# phase2.net
KiCad netlist of a schematic drawn in EAGLE
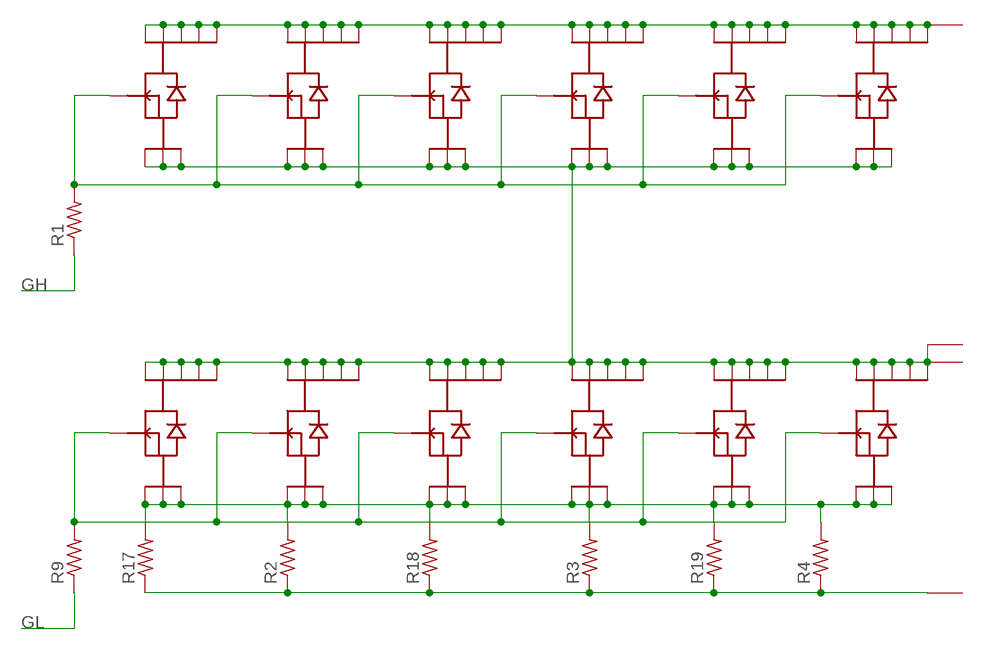
[diagram p0: schematic, sheet 1]

(export (version "E")
  (design (tool "Eeschema 10.0.6"))
  (components
    (comp (ref "R1")
      (value "R-US_R1206")
      (footprint "eagle-import:R1206")
      (libsource (lib "eagle-import") (part "R-US_R1206"))
    )
    (comp (ref "R2")
      (value "R-US_M1206")
      (footprint "eagle-import:M1206")
      (libsource (lib "eagle-import") (part "R-US_M1206"))
    )
    (comp (ref "R3")
      (value "R-US_M1206")
      (footprint "eagle-import:M1206")
      (libsource (lib "eagle-import") (part "R-US_M1206"))
    )
    (comp (ref "R4")
      (value "R-US_M1206")
      (footprint "eagle-import:M1206")
      (libsource (lib "eagle-import") (part "R-US_M1206"))
    )
    (comp (ref "R9")
      (value "R-US_R1206")
      (footprint "eagle-import:R1206")
      (libsource (lib "eagle-import") (part "R-US_R1206"))
    )
    (comp (ref "R17")
      (value "R-US_M1206")
      (footprint "eagle-import:M1206")
      (libsource (lib "eagle-import") (part "R-US_M1206"))
    )
    (comp (ref "R18")
      (value "R-US_M1206")
      (footprint "eagle-import:M1206")
      (libsource (lib "eagle-import") (part "R-US_M1206"))
    )
    (comp (ref "R19")
      (value "R-US_M1206")
      (footprint "eagle-import:M1206")
      (libsource (lib "eagle-import") (part "R-US_M1206"))
    )
    (comp (ref "U$1")
      (value "TPH2R608NH")
      (footprint "eagle-import:SOP-ADVANCE")
      (libsource (lib "eagle-import") (part "TPH2R608NH"))
    )
    (comp (ref "U$2")
      (value "TPH2R608NH")
      (footprint "eagle-import:SOP-ADVANCE")
      (libsource (lib "eagle-import") (part "TPH2R608NH"))
    )
    (comp (ref "U$3")
      (value "TPH2R608NH")
      (footprint "eagle-import:SOP-ADVANCE")
      (libsource (lib "eagle-import") (part "TPH2R608NH"))
    )
    (comp (ref "U$4")
      (value "TPH2R608NH")
      (footprint "eagle-import:SOP-ADVANCE")
      (libsource (lib "eagle-import") (part "TPH2R608NH"))
    )
    (comp (ref "U$5")
      (value "TPH2R608NH")
      (footprint "eagle-import:SOP-ADVANCE")
      (libsource (lib "eagle-import") (part "TPH2R608NH"))
    )
    (comp (ref "U$6")
      (value "TPH2R608NH")
      (footprint "eagle-import:SOP-ADVANCE")
      (libsource (lib "eagle-import") (part "TPH2R608NH"))
    )
    (comp (ref "U$9")
      (value "TPH2R608NH")
      (footprint "eagle-import:SOP-ADVANCE")
      (libsource (lib "eagle-import") (part "TPH2R608NH"))
    )
    (comp (ref "U$10")
      (value "TPH2R608NH")
      (footprint "eagle-import:SOP-ADVANCE")
      (libsource (lib "eagle-import") (part "TPH2R608NH"))
    )
    (comp (ref "U$11")
      (value "TPH2R608NH")
      (footprint "eagle-import:SOP-ADVANCE")
      (libsource (lib "eagle-import") (part "TPH2R608NH"))
    )
    (comp (ref "U$12")
      (value "TPH2R608NH")
      (footprint "eagle-import:SOP-ADVANCE")
      (libsource (lib "eagle-import") (part "TPH2R608NH"))
    )
    (comp (ref "U$13")
      (value "TPH2R608NH")
      (footprint "eagle-import:SOP-ADVANCE")
      (libsource (lib "eagle-import") (part "TPH2R608NH"))
    )
    (comp (ref "U$14")
      (value "TPH2R608NH")
      (footprint "eagle-import:SOP-ADVANCE")
      (libsource (lib "eagle-import") (part "TPH2R608NH"))
    )
    (comp (ref "U$17")
      (value "BUSBAR")
      (footprint "eagle-import:BUSBAR")
      (libsource (lib "eagle-import") (part "BUSBAR"))
    )
    (comp (ref "U$18")
      (value "BUSBAR")
      (footprint "eagle-import:BUSBAR")
      (libsource (lib "eagle-import") (part "BUSBAR"))
    )
    (comp (ref "U$19")
      (value "BUSBAR")
      (footprint "eagle-import:BUSBAR")
      (libsource (lib "eagle-import") (part "BUSBAR"))
    )
    (comp (ref "U$20")
      (value "POWERPAD")
      (footprint "eagle-import:POWERPAD")
      (libsource (lib "eagle-import") (part "POWERPAD"))
    )
  )
  (nets
    (net (code "1") (name "/GH") (class "Default")
      (node (ref "R1") (pin "1") (pinfunction "1_1") (pintype "passive"))
    )
    (net (code "2") (name "/GL") (class "Default")
      (node (ref "R9") (pin "1") (pinfunction "1_1") (pintype "passive"))
    )
    (net (code "3") (name "Net-(R17-Pad1)") (class "Default")
      (node (ref "R17") (pin "1") (pinfunction "1_1") (pintype "passive"))
      (node (ref "R18") (pin "1") (pinfunction "1_1") (pintype "passive"))
      (node (ref "R19") (pin "1") (pinfunction "1_1") (pintype "passive"))
      (node (ref "R2") (pin "1") (pinfunction "1_1") (pintype "passive"))
      (node (ref "R3") (pin "1") (pinfunction "1_1") (pintype "passive"))
      (node (ref "R4") (pin "1") (pinfunction "1_1") (pintype "passive"))
      (node (ref "U$19") (pin "P$1") (pinfunction "P$1_P$1") (pintype "bidirectional"))
    )
    (net (code "4") (name "Net-(U$1-D1)") (class "Default")
      (node (ref "U$1") (pin "5") (pinfunction "D1_5") (pintype "bidirectional"))
      (node (ref "U$1") (pin "6") (pinfunction "D2_6") (pintype "bidirectional"))
      (node (ref "U$1") (pin "7") (pinfunction "D3_7") (pintype "bidirectional"))
      (node (ref "U$1") (pin "8") (pinfunction "D4_8") (pintype "bidirectional"))
      (node (ref "U$1") (pin "9") (pinfunction "DTAB_9") (pintype "bidirectional"))
      (node (ref "U$17") (pin "P$1") (pinfunction "P$1_P$1") (pintype "bidirectional"))
      (node (ref "U$2") (pin "5") (pinfunction "D1_5") (pintype "bidirectional"))
      (node (ref "U$2") (pin "6") (pinfunction "D2_6") (pintype "bidirectional"))
      (node (ref "U$2") (pin "7") (pinfunction "D3_7") (pintype "bidirectional"))
      (node (ref "U$2") (pin "8") (pinfunction "D4_8") (pintype "bidirectional"))
      (node (ref "U$2") (pin "9") (pinfunction "DTAB_9") (pintype "bidirectional"))
      (node (ref "U$3") (pin "5") (pinfunction "D1_5") (pintype "bidirectional"))
      (node (ref "U$3") (pin "6") (pinfunction "D2_6") (pintype "bidirectional"))
      (node (ref "U$3") (pin "7") (pinfunction "D3_7") (pintype "bidirectional"))
      (node (ref "U$3") (pin "8") (pinfunction "D4_8") (pintype "bidirectional"))
      (node (ref "U$3") (pin "9") (pinfunction "DTAB_9") (pintype "bidirectional"))
      (node (ref "U$4") (pin "5") (pinfunction "D1_5") (pintype "bidirectional"))
      (node (ref "U$4") (pin "6") (pinfunction "D2_6") (pintype "bidirectional"))
      (node (ref "U$4") (pin "7") (pinfunction "D3_7") (pintype "bidirectional"))
      (node (ref "U$4") (pin "8") (pinfunction "D4_8") (pintype "bidirectional"))
      (node (ref "U$4") (pin "9") (pinfunction "DTAB_9") (pintype "bidirectional"))
      (node (ref "U$5") (pin "5") (pinfunction "D1_5") (pintype "bidirectional"))
      (node (ref "U$5") (pin "6") (pinfunction "D2_6") (pintype "bidirectional"))
      (node (ref "U$5") (pin "7") (pinfunction "D3_7") (pintype "bidirectional"))
      (node (ref "U$5") (pin "8") (pinfunction "D4_8") (pintype "bidirectional"))
      (node (ref "U$5") (pin "9") (pinfunction "DTAB_9") (pintype "bidirectional"))
      (node (ref "U$6") (pin "5") (pinfunction "D1_5") (pintype "bidirectional"))
      (node (ref "U$6") (pin "6") (pinfunction "D2_6") (pintype "bidirectional"))
      (node (ref "U$6") (pin "7") (pinfunction "D3_7") (pintype "bidirectional"))
      (node (ref "U$6") (pin "8") (pinfunction "D4_8") (pintype "bidirectional"))
      (node (ref "U$6") (pin "9") (pinfunction "DTAB_9") (pintype "bidirectional"))
    )
    (net (code "5") (name "Net-(U$1-G)") (class "Default")
      (node (ref "R1") (pin "2") (pinfunction "2_2") (pintype "passive"))
      (node (ref "U$1") (pin "4") (pinfunction "G_4") (pintype "bidirectional"))
      (node (ref "U$2") (pin "4") (pinfunction "G_4") (pintype "bidirectional"))
      (node (ref "U$3") (pin "4") (pinfunction "G_4") (pintype "bidirectional"))
      (node (ref "U$4") (pin "4") (pinfunction "G_4") (pintype "bidirectional"))
      (node (ref "U$5") (pin "4") (pinfunction "G_4") (pintype "bidirectional"))
      (node (ref "U$6") (pin "4") (pinfunction "G_4") (pintype "bidirectional"))
    )
    (net (code "6") (name "Net-(U$1-S1)") (class "Default")
      (node (ref "U$1") (pin "1") (pinfunction "S1_1") (pintype "bidirectional"))
      (node (ref "U$1") (pin "2") (pinfunction "S2_2") (pintype "bidirectional"))
      (node (ref "U$1") (pin "3") (pinfunction "S3_3") (pintype "bidirectional"))
      (node (ref "U$10") (pin "5") (pinfunction "D1_5") (pintype "bidirectional"))
      (node (ref "U$10") (pin "6") (pinfunction "D2_6") (pintype "bidirectional"))
      (node (ref "U$10") (pin "7") (pinfunction "D3_7") (pintype "bidirectional"))
      (node (ref "U$10") (pin "8") (pinfunction "D4_8") (pintype "bidirectional"))
      (node (ref "U$10") (pin "9") (pinfunction "DTAB_9") (pintype "bidirectional"))
      (node (ref "U$11") (pin "5") (pinfunction "D1_5") (pintype "bidirectional"))
      (node (ref "U$11") (pin "6") (pinfunction "D2_6") (pintype "bidirectional"))
      (node (ref "U$11") (pin "7") (pinfunction "D3_7") (pintype "bidirectional"))
      (node (ref "U$11") (pin "8") (pinfunction "D4_8") (pintype "bidirectional"))
      (node (ref "U$11") (pin "9") (pinfunction "DTAB_9") (pintype "bidirectional"))
      (node (ref "U$12") (pin "5") (pinfunction "D1_5") (pintype "bidirectional"))
      (node (ref "U$12") (pin "6") (pinfunction "D2_6") (pintype "bidirectional"))
      (node (ref "U$12") (pin "7") (pinfunction "D3_7") (pintype "bidirectional"))
      (node (ref "U$12") (pin "8") (pinfunction "D4_8") (pintype "bidirectional"))
      (node (ref "U$12") (pin "9") (pinfunction "DTAB_9") (pintype "bidirectional"))
      (node (ref "U$13") (pin "5") (pinfunction "D1_5") (pintype "bidirectional"))
      (node (ref "U$13") (pin "6") (pinfunction "D2_6") (pintype "bidirectional"))
      (node (ref "U$13") (pin "7") (pinfunction "D3_7") (pintype "bidirectional"))
      (node (ref "U$13") (pin "8") (pinfunction "D4_8") (pintype "bidirectional"))
      (node (ref "U$13") (pin "9") (pinfunction "DTAB_9") (pintype "bidirectional"))
      (node (ref "U$14") (pin "5") (pinfunction "D1_5") (pintype "bidirectional"))
      (node (ref "U$14") (pin "6") (pinfunction "D2_6") (pintype "bidirectional"))
      (node (ref "U$14") (pin "7") (pinfunction "D3_7") (pintype "bidirectional"))
      (node (ref "U$14") (pin "8") (pinfunction "D4_8") (pintype "bidirectional"))
      (node (ref "U$14") (pin "9") (pinfunction "DTAB_9") (pintype "bidirectional"))
      (node (ref "U$18") (pin "P$1") (pinfunction "P$1_P$1") (pintype "bidirectional"))
      (node (ref "U$2") (pin "1") (pinfunction "S1_1") (pintype "bidirectional"))
      (node (ref "U$2") (pin "2") (pinfunction "S2_2") (pintype "bidirectional"))
      (node (ref "U$2") (pin "3") (pinfunction "S3_3") (pintype "bidirectional"))
      (node (ref "U$20") (pin "P$1") (pinfunction "P$1_P$1") (pintype "bidirectional"))
      (node (ref "U$3") (pin "1") (pinfunction "S1_1") (pintype "bidirectional"))
      (node (ref "U$3") (pin "2") (pinfunction "S2_2") (pintype "bidirectional"))
      (node (ref "U$3") (pin "3") (pinfunction "S3_3") (pintype "bidirectional"))
      (node (ref "U$4") (pin "1") (pinfunction "S1_1") (pintype "bidirectional"))
      (node (ref "U$4") (pin "2") (pinfunction "S2_2") (pintype "bidirectional"))
      (node (ref "U$4") (pin "3") (pinfunction "S3_3") (pintype "bidirectional"))
      (node (ref "U$5") (pin "1") (pinfunction "S1_1") (pintype "bidirectional"))
      (node (ref "U$5") (pin "2") (pinfunction "S2_2") (pintype "bidirectional"))
      (node (ref "U$5") (pin "3") (pinfunction "S3_3") (pintype "bidirectional"))
      (node (ref "U$6") (pin "1") (pinfunction "S1_1") (pintype "bidirectional"))
      (node (ref "U$6") (pin "2") (pinfunction "S2_2") (pintype "bidirectional"))
      (node (ref "U$6") (pin "3") (pinfunction "S3_3") (pintype "bidirectional"))
      (node (ref "U$9") (pin "5") (pinfunction "D1_5") (pintype "bidirectional"))
      (node (ref "U$9") (pin "6") (pinfunction "D2_6") (pintype "bidirectional"))
      (node (ref "U$9") (pin "7") (pinfunction "D3_7") (pintype "bidirectional"))
      (node (ref "U$9") (pin "8") (pinfunction "D4_8") (pintype "bidirectional"))
      (node (ref "U$9") (pin "9") (pinfunction "DTAB_9") (pintype "bidirectional"))
    )
    (net (code "7") (name "Net-(U$10-G)") (class "Default")
      (node (ref "R9") (pin "2") (pinfunction "2_2") (pintype "passive"))
      (node (ref "U$10") (pin "4") (pinfunction "G_4") (pintype "bidirectional"))
      (node (ref "U$11") (pin "4") (pinfunction "G_4") (pintype "bidirectional"))
      (node (ref "U$12") (pin "4") (pinfunction "G_4") (pintype "bidirectional"))
      (node (ref "U$13") (pin "4") (pinfunction "G_4") (pintype "bidirectional"))
      (node (ref "U$14") (pin "4") (pinfunction "G_4") (pintype "bidirectional"))
      (node (ref "U$9") (pin "4") (pinfunction "G_4") (pintype "bidirectional"))
    )
    (net (code "8") (name "Net-(U$10-S1)") (class "Default")
      (node (ref "R17") (pin "2") (pinfunction "2_2") (pintype "passive"))
      (node (ref "R18") (pin "2") (pinfunction "2_2") (pintype "passive"))
      (node (ref "R19") (pin "2") (pinfunction "2_2") (pintype "passive"))
      (node (ref "R2") (pin "2") (pinfunction "2_2") (pintype "passive"))
      (node (ref "R3") (pin "2") (pinfunction "2_2") (pintype "passive"))
      (node (ref "R4") (pin "2") (pinfunction "2_2") (pintype "passive"))
      (node (ref "U$10") (pin "1") (pinfunction "S1_1") (pintype "bidirectional"))
      (node (ref "U$10") (pin "2") (pinfunction "S2_2") (pintype "bidirectional"))
      (node (ref "U$10") (pin "3") (pinfunction "S3_3") (pintype "bidirectional"))
      (node (ref "U$11") (pin "1") (pinfunction "S1_1") (pintype "bidirectional"))
      (node (ref "U$11") (pin "2") (pinfunction "S2_2") (pintype "bidirectional"))
      (node (ref "U$11") (pin "3") (pinfunction "S3_3") (pintype "bidirectional"))
      (node (ref "U$12") (pin "1") (pinfunction "S1_1") (pintype "bidirectional"))
      (node (ref "U$12") (pin "2") (pinfunction "S2_2") (pintype "bidirectional"))
      (node (ref "U$12") (pin "3") (pinfunction "S3_3") (pintype "bidirectional"))
      (node (ref "U$13") (pin "1") (pinfunction "S1_1") (pintype "bidirectional"))
      (node (ref "U$13") (pin "2") (pinfunction "S2_2") (pintype "bidirectional"))
      (node (ref "U$13") (pin "3") (pinfunction "S3_3") (pintype "bidirectional"))
      (node (ref "U$14") (pin "1") (pinfunction "S1_1") (pintype "bidirectional"))
      (node (ref "U$14") (pin "2") (pinfunction "S2_2") (pintype "bidirectional"))
      (node (ref "U$14") (pin "3") (pinfunction "S3_3") (pintype "bidirectional"))
      (node (ref "U$9") (pin "1") (pinfunction "S1_1") (pintype "bidirectional"))
      (node (ref "U$9") (pin "2") (pinfunction "S2_2") (pintype "bidirectional"))
      (node (ref "U$9") (pin "3") (pinfunction "S3_3") (pintype "bidirectional"))
    )
  )
)
